# XC4216_DC_DC5V.net
KiCad netlist of a schematic drawn in Altium Designer
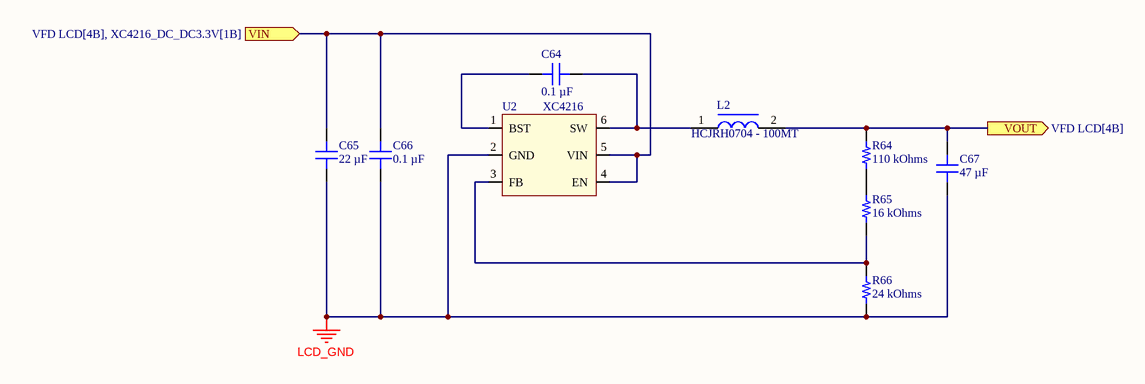
[diagram p0: XC4216_DC_DC5V.SchDoc]

(export (version "E")
  (design (tool "Eeschema 10.0.6"))
  (components
    (comp (ref "C64")
      (value "0.1 µF")
      (footprint "CAP 0805_2012")
      (description "CAP CER 0.1UF 50V X7R 0805")
      (fields (field (name "PART NUMBER") "CC0805MRX7R9BB104") (field (name "MANUFACTURER") "Yageo"))
      (libsource (lib "Celestial Altium Library - altium_library") (part "Capacitor"))
    )
    (comp (ref "C65")
      (value "22 µF")
      (footprint "CAP 0805_2012")
      (description "CAP CER 22UF 6.3V X6S 0805")
      (fields
        (field (name "PART NUMBER") "C2012X6S0J226M125AB")
        (field (name "MANUFACTURER") "TDK Corporation")
      )
      (libsource (lib "Celestial Altium Library - altium_library") (part "Capacitor"))
    )
    (comp (ref "C66")
      (value "0.1 µF")
      (footprint "CAP 0805_2012")
      (description "CAP CER 0.1UF 50V X7R 0805")
      (fields (field (name "PART NUMBER") "CC0805MRX7R9BB104") (field (name "MANUFACTURER") "Yageo"))
      (libsource (lib "Celestial Altium Library - altium_library") (part "Capacitor"))
    )
    (comp (ref "C67")
      (value "47 µF")
      (footprint "CAP 0805_2012")
      (description "CAP CER 47UF 4V X5R 0805")
      (fields (field (name "PART NUMBER") "AMK212BBJ476MD-T") (field (name "MANUFACTURER") "Taiyo Yuden"))
      (libsource (lib "Celestial Altium Library - altium_library") (part "Capacitor"))
    )
    (comp (ref "L2")
      (value "HCJRH0704 - 100MT")
      (footprint "HCJRH0704 - 100MT")
      (description "Inductor 10UH")
      (libsource (lib "My altlib") (part "HCJRH0704 - 100MT"))
    )
    (comp (ref "R64")
      (value "110 kOhms")
      (footprint "RES 0805_2012")
      (description "RES SMD 110K OHM 1% 1/8W 0805")
      (fields (field (name "PART NUMBER") "CRCW0805110KFKEA") (field (name "MANUFACTURER") "Vishay Dale"))
      (libsource (lib "Celestial Altium Library - altium_library") (part "Resistor"))
    )
    (comp (ref "R65")
      (value "16 kOhms")
      (footprint "RES 0805_2012")
      (description "RES SMD 16K OHM 1% 1/8W 0805")
      (fields (field (name "PART NUMBER") "CRCW080516K0FKEA") (field (name "MANUFACTURER") "Vishay Dale"))
      (libsource (lib "Celestial Altium Library - altium_library") (part "Resistor"))
    )
    (comp (ref "R66")
      (value "24 kOhms")
      (footprint "RES 0805_2012")
      (description "RES 24K OHM 0.1% 1/8W 0805")
      (fields (field (name "PART NUMBER") "TNPW080524K0BEEA") (field (name "MANUFACTURER") "Vishay Dale"))
      (libsource (lib "Celestial Altium Library - altium_library") (part "Resistor"))
    )
    (comp (ref "U2") (value "XC4216") (footprint "SOT-23-6") (libsource (lib "My altlib") (part "XC4216")))
  )
  (nets
    (net (code "1") (name "/VIN") (class "Default")
      (node (ref "C65") (pin "2") (pinfunction "2_2") (pintype "passive"))
      (node (ref "C66") (pin "2") (pinfunction "2_2") (pintype "passive"))
      (node (ref "U2") (pin "4") (pinfunction "EN_4") (pintype "passive"))
      (node (ref "U2") (pin "5") (pinfunction "VIN_5") (pintype "passive"))
    )
    (net (code "2") (name "/VOUT") (class "Default")
      (node (ref "C67") (pin "2") (pinfunction "2_2") (pintype "passive"))
      (node (ref "L2") (pin "2") (pinfunction "6_2") (pintype "passive"))
      (node (ref "R64") (pin "2") (pinfunction "2_2") (pintype "passive"))
    )
    (net (code "3") (name "LCD_GND") (class "Default")
      (node (ref "C65") (pin "1") (pinfunction "1_1") (pintype "passive"))
      (node (ref "C66") (pin "1") (pinfunction "1_1") (pintype "passive"))
      (node (ref "C67") (pin "1") (pinfunction "1_1") (pintype "passive"))
      (node (ref "R66") (pin "1") (pinfunction "1_1") (pintype "passive"))
      (node (ref "U2") (pin "2") (pinfunction "GND_2") (pintype "passive"))
    )
    (net (code "4") (name "Net-(R64-Pad1)") (class "Default")
      (node (ref "R64") (pin "1") (pinfunction "1_1") (pintype "passive"))
      (node (ref "R65") (pin "2") (pinfunction "2_2") (pintype "passive"))
    )
    (net (code "5") (name "Net-(U2-BST)") (class "Default")
      (node (ref "C64") (pin "1") (pinfunction "1_1") (pintype "passive"))
      (node (ref "U2") (pin "1") (pinfunction "BST_1") (pintype "passive"))
    )
    (net (code "6") (name "Net-(U2-FB)") (class "Default")
      (node (ref "R65") (pin "1") (pinfunction "1_1") (pintype "passive"))
      (node (ref "R66") (pin "2") (pinfunction "2_2") (pintype "passive"))
      (node (ref "U2") (pin "3") (pinfunction "FB_3") (pintype "passive"))
    )
    (net (code "7") (name "Net-(U2-SW)") (class "Default")
      (node (ref "C64") (pin "2") (pinfunction "2_2") (pintype "passive"))
      (node (ref "L2") (pin "1") (pinfunction "6_1") (pintype "passive"))
      (node (ref "U2") (pin "6") (pinfunction "SW_6") (pintype "passive"))
    )
  )
)
